# JacdacTactEc30_115.net
KiCad netlist of a schematic drawn in Altium Designer
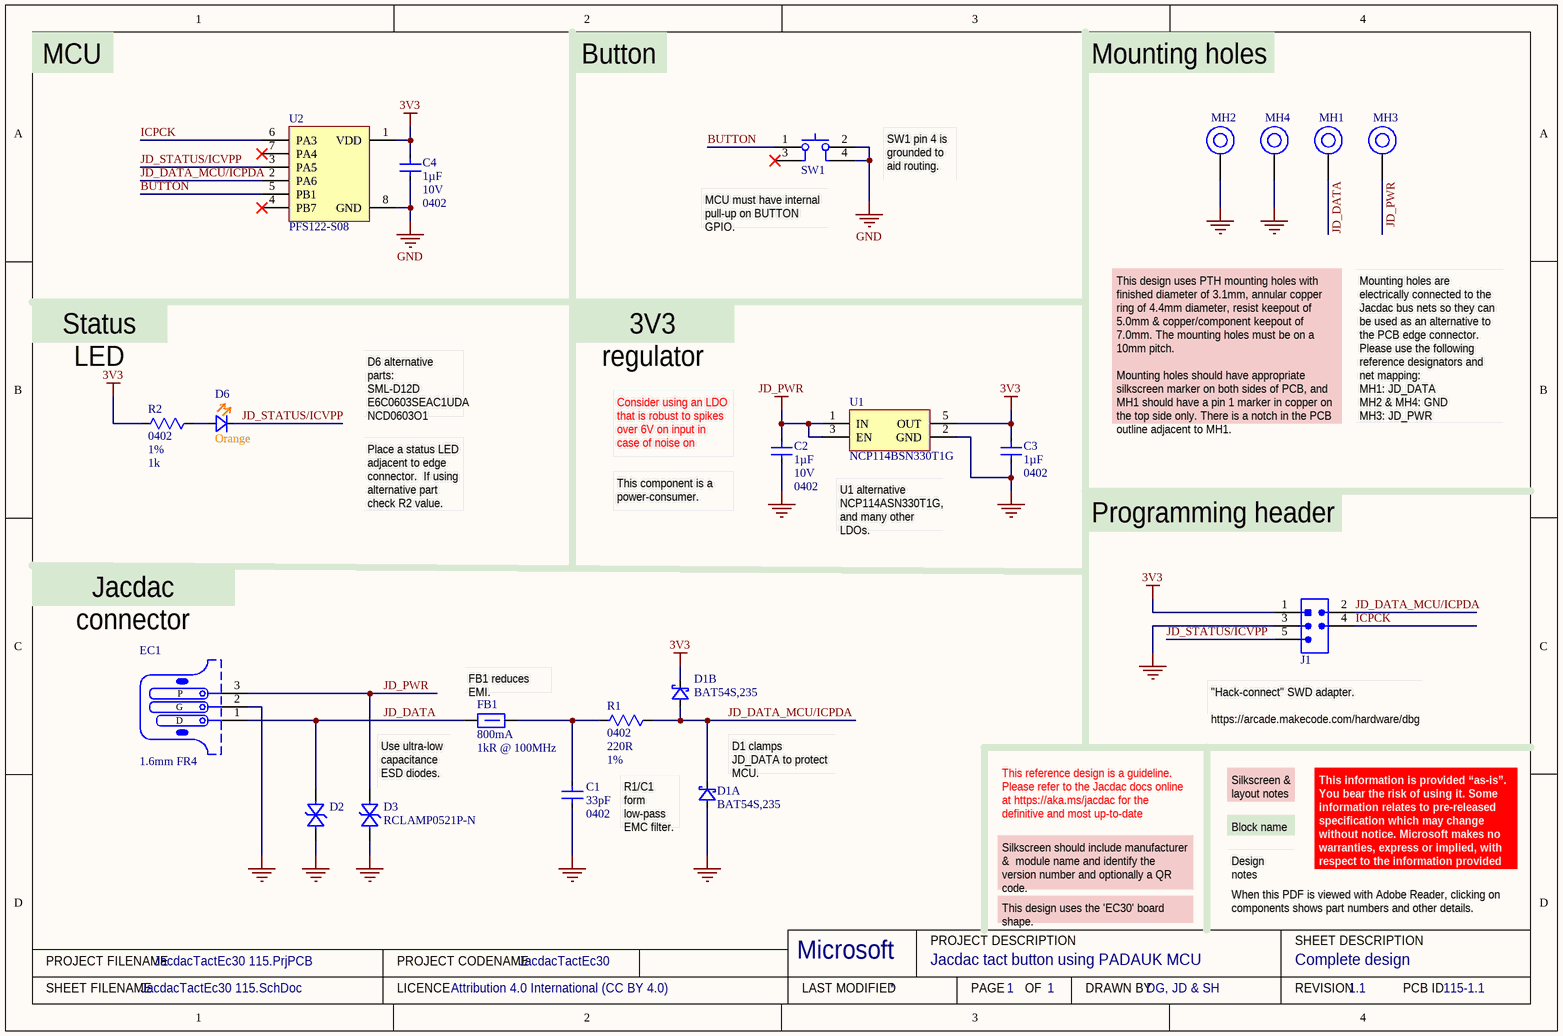
[diagram p0: JacdacTactEc30 115.SchDoc]

(export (version "E")
  (design (tool "Eeschema 10.0.6"))
  (components
    (comp (ref "C1")
      (value "CL05C330JB5NNNC")
      (footprint "C0402_0.55MM - without outline")
      (description "CAP CER 33PF 50V C0G/NP0 0402")
      (fields
        (field (name "MANUFACTURER") "Samsung")
        (field (name "CASE CODE (IMPERIAL)") "0402")
        (field (name "TOLERANCE") "5%")
        (field (name "CAPACITANCE") "33pF")
      )
      (libsource (lib "Samsung") (part "CL05C330JB5NNNC"))
    )
    (comp (ref "C2")
      (value "CL05A105KP5NNNC")
      (footprint "C0402_0.55MM - without outline")
      (description "CAP CER 1UF 10V X5R 0402")
      (fields
        (field (name "MANUFACTURER") "Samsung")
        (field (name "TOLERANCE") "10%")
        (field (name "CAPACITANCE") "1µF")
        (field (name "VOLTAGE RATING") "10V")
        (field (name "CASE CODE (IMPERIAL)") "0402")
        (field (name "CREATED") "DG")
        (field (name "CHECKED") "?")
      )
      (libsource (lib "Samsung") (part "CL05A105KP5NNNC"))
    )
    (comp (ref "C3")
      (value "CL05A105KP5NNNC")
      (footprint "C0402_0.55MM - without outline")
      (description "CAP CER 1UF 10V X5R 0402")
      (fields
        (field (name "MANUFACTURER") "Samsung")
        (field (name "TOLERANCE") "10%")
        (field (name "CAPACITANCE") "1µF")
        (field (name "CASE CODE (IMPERIAL)") "0402")
        (field (name "CREATED") "DG")
        (field (name "CHECKED") "?")
      )
      (libsource (lib "Samsung") (part "CL05A105KP5NNNC"))
    )
    (comp (ref "C4")
      (value "CL05A105KP5NNNC")
      (footprint "C0402_0.55MM - without outline")
      (description "CAP CER 1UF 10V X5R 0402")
      (fields
        (field (name "MANUFACTURER") "Samsung")
        (field (name "TOLERANCE") "10%")
        (field (name "CAPACITANCE") "1µF")
        (field (name "VOLTAGE RATING") "10V")
        (field (name "CASE CODE (IMPERIAL)") "0402")
        (field (name "CREATED") "DG")
        (field (name "CHECKED") "?")
      )
      (libsource (lib "Samsung") (part "CL05A105KP5NNNC"))
    )
    (comp (ref "D1")
      (value "BAT54S")
      (footprint "NXP-BAT54S-TO-236AB - without outline")
      (description "DIODE ARRAY SCHOTTKY 30V SOT23")
      (fields (field (name "MANUFACTURER") "Nexperia") (field (name "MANUFACTURER PART NUMBER") "BAT54S,235"))
      (libsource (lib "NXP") (part "BAT54S"))
    )
    (comp (ref "D2")
      (value "RCLAMP0521P-N")
      (footprint "0402:TVS 0402 - XL")
      (description "Bidirectional 5V (Max) 6V 16V 3.5A (8/20us) 0402 TVS RoHS")
      (fields
        (field (name "MANUFACTURER") "Born Semiconductor")
        (field (name "CREATED BY") "D Gakure")
        (field (name "CHECKED BY") "?")
      )
      (libsource (lib "BornSemiconductor") (part "RCLAMP0521P-N"))
    )
    (comp (ref "D3")
      (value "RCLAMP0521P-N")
      (footprint "0402:TVS 0402 - XL")
      (description "Bidirectional 5V (Max) 6V 16V 3.5A (8/20us) 0402 TVS RoHS")
      (fields
        (field (name "MANUFACTURER") "Born Semiconductor")
        (field (name "MANUFACTURER PART NUMBER") "RCLAMP0521P-N")
        (field (name "CREATED BY") "D Gakure")
        (field (name "CHECKED BY") "?")
      )
      (libsource (lib "BornSemiconductor") (part "RCLAMP0521P-N"))
    )
    (comp (ref "D6")
      (value "~")
      (footprint "0603 Orange - without outline")
      (description "LED ORANGE DIFFUSED 1608 SMD")
      (fields
        (field (name "MANUFACTURER") "Everlight Elec")
        (field (name "MANUFACTURER PART NUMBER") "19-217/S2C-AQ1R1B/3T")
        (field (name "COLOUR") "Orange")
      )
      (libsource (lib "EverlightElec") (part "19-217/S2C-AQ1R1B/3T"))
    )
    (comp (ref "EC1")
      (value "3 pin JACDAC edge connector")
      (footprint "JACDAC_edge_connector:JACDAC_EDGE_CONNECTOR_NO_TRACES")
      (description "3 pin Jacdac edge connector 1.27mm pitch")
      (fields
        (field (name "MANUFACTURER PART NUMBER") "JACDAC_EDGE_CONNECTOR")
        (field (name "PCB TYPE") "1.6mm FR4")
        (field (name "CHECKED BY") "?")
        (field (name "CREATED BY") "D. Gakure")
      )
      (libsource (lib "generic-con") (part "Jacdac edge connector"))
    )
    (comp (ref "FB1")
      (value "TDK MPZ1608S102ATA00")
      (footprint "TDK MPZ1608 0.8mm - without outline")
      (description "0603 1k@100MHz 0.8A chip")
      (fields
        (field (name "TOLERANCE") "25%")
        (field (name "MANUFACTURER") "TDK")
        (field (name "CURRENT RATING") "800mA")
        (field (name "IMPEDANCE") "1kR @ 100MHz")
      )
      (libsource (lib "TDK") (part "TDK MPZ1608S102ATA00"))
    )
    (comp (ref "J1")
      (value "Hack Connect Mini 1.27 mm pitch 2-row")
      (footprint "HackConnect:HACK_CONNECT_MINI_5_X_1_27_0.559mm_TH")
      (libsource (lib "generic-con") (part "HACK_CONNECT_MINI"))
    )
    (comp (ref "MH1")
      (value "MH_7.0MMK_4.4MMC_3.1MMD_PTH")
      (footprint "MH_7.0MMK_4.4MMC_3.1MMD_PTH:MH_7.0MMK_4.4MMC_3.1MMD_PTH")
      (description "Mounting Hole 7.0mm keepout, 4.4mm annualar ring and 3.1mm Drill PTH")
      (libsource (lib "generic") (part "MH_7.0MMK_4.4MMC_3.1MMD_PTH"))
    )
    (comp (ref "MH2")
      (value "MH_7.0MMK_4.4MMC_3.1MMD_PTH")
      (footprint "MH_7.0MMK_4.4MMC_3.1MMD_PTH:MH_7.0MMK_4.4MMC_3.1MMD_PTH")
      (description "Mounting Hole 7.0mm keepout, 4.4mm annualar ring and 3.1mm Drill PTH")
      (libsource (lib "generic") (part "MH_7.0MMK_4.4MMC_3.1MMD_PTH"))
    )
    (comp (ref "MH3")
      (value "MH_7.0MMK_4.4MMC_3.1MMD_PTH")
      (footprint "MH_7.0MMK_4.4MMC_3.1MMD_PTH:MH_7.0MMK_4.4MMC_3.1MMD_PTH")
      (description "Mounting Hole 7.0mm keepout, 4.4mm annualar ring and 3.1mm Drill PTH")
      (libsource (lib "generic") (part "MH_7.0MMK_4.4MMC_3.1MMD_PTH"))
    )
    (comp (ref "MH4")
      (value "MH_7.0MMK_4.4MMC_3.1MMD_PTH")
      (footprint "MH_7.0MMK_4.4MMC_3.1MMD_PTH:MH_7.0MMK_4.4MMC_3.1MMD_PTH")
      (description "Mounting Hole 7.0mm keepout, 4.4mm annualar ring and 3.1mm Drill PTH")
      (libsource (lib "generic") (part "MH_7.0MMK_4.4MMC_3.1MMD_PTH"))
    )
    (comp (ref "R1")
      (value "RC0402FR-07220RL")
      (footprint "R0402 - Without outline")
      (description "RES SMD 220 OHM 1% 1/16W 0402")
      (fields
        (field (name "MANUFACTURER") "Yageo")
        (field (name "CASE CODE (IMPERIAL)") "0402")
        (field (name "RESISTANCE") "220R")
        (field (name "TOLERANCE") "1%")
        (field (name "CREATED") "D.G")
        (field (name "CHECKED") "?")
      )
      (libsource (lib "Yageo") (part "RC0402FR-07220RL"))
    )
    (comp (ref "R2")
      (value "RC0402FR-071KL")
      (footprint "R0402 - Without outline")
      (description "RES SMD 1K OHM 1% 1/16W 0402")
      (fields
        (field (name "MANUFACTURER") "Yageo")
        (field (name "CASE CODE (IMPERIAL)") "0402")
        (field (name "TOLERANCE") "1%")
        (field (name "RESISTANCE") "1k")
        (field (name "CREATED") "D.G")
        (field (name "CHECKED") "?")
      )
      (libsource (lib "Yageo") (part "RC0402FR-071KL"))
    )
    (comp (ref "SW1")
      (value "Tact Wurth 430152050826")
      (footprint "Wurth 430152050836-WIDE")
      (description "6x6mm SPST 0.05A 12VDC SMD 260gf")
      (fields
        (field (name "MANUFACTURER") "Wurth Electronics")
        (field (name "MANUFACTURER PART NUMBER") "430152050826")
      )
      (libsource (lib "Wurth") (part "Tact Wurth 430152050826"))
    )
    (comp (ref "U1")
      (value "LDO 3.3V/300 mA")
      (footprint "ON_SEMI-SOT23-5 - without outline")
      (description "CMOS Low Dropout Regulator (LDO), 300 mA 3.3V, Non-Active Discharge, TSOP5")
      (fields
        (field (name "MANUFACTURER") "ON Semiconductor")
        (field (name "MANUFACTURER PART NUMBER") "NCP114BSN330T1G")
      )
      (libsource (lib "OnSemiconductor") (part "NCP114BSN330T1G"))
    )
    (comp (ref "U2")
      (value "PFS122-S08")
      (footprint "PADAUK-SOP-8:SOP-8")
      (description "8bit MTP MCU with 12-bit ADC")
      (fields (field (name "MANUFACTURER") "PADAUK") (field (name "MANUFACTURER PART NUMBER") "PFS122-S08"))
      (libsource (lib "PADAUK") (part "PFS122-SO8"))
    )
  )
  (nets
    (net (code "1") (name "/BUTTON") (class "Default")
      (node (ref "SW1") (pin "1") (pinfunction "1_1") (pintype "passive"))
      (node (ref "U2") (pin "5") (pinfunction "PB1_5") (pintype "passive"))
    )
    (net (code "2") (name "/ICPCK") (class "Default")
      (node (ref "J1") (pin "4") (pinfunction "SWCLK_4") (pintype "passive"))
      (node (ref "U2") (pin "6") (pinfunction "PA3_6") (pintype "passive"))
    )
    (net (code "3") (name "/JD_DATA") (class "Default")
      (node (ref "D2") (pin "1") (pinfunction "K_1") (pintype "passive"))
      (node (ref "EC1") (pin "1") (pinfunction "D_1") (pintype "passive"))
      (node (ref "FB1") (pin "1") (pinfunction "1_1") (pintype "passive"))
      (node (ref "MH1") (pin "1") (pinfunction "1_1") (pintype "passive"))
    )
    (net (code "4") (name "/JD_DATA_MCU{slash}ICPDA") (class "Default")
      (node (ref "D1") (pin "3") (pinfunction "A_3") (pintype "passive"))
      (node (ref "J1") (pin "2") (pinfunction "SWDIO_2") (pintype "passive"))
      (node (ref "R1") (pin "1") (pinfunction "1_1") (pintype "passive"))
      (node (ref "U2") (pin "2") (pinfunction "PA6_2") (pintype "passive"))
    )
    (net (code "5") (name "/JD_STATUS{slash}ICVPP") (class "Default")
      (node (ref "D6") (pin "1") (pinfunction "K_1") (pintype "passive"))
      (node (ref "J1") (pin "5") (pinfunction "RESET_5") (pintype "passive"))
      (node (ref "U2") (pin "3") (pinfunction "PA5_3") (pintype "passive"))
    )
    (net (code "6") (name "3V3") (class "Default")
      (node (ref "C3") (pin "2") (pinfunction "2_2") (pintype "passive"))
      (node (ref "C4") (pin "2") (pinfunction "2_2") (pintype "passive"))
      (node (ref "D1") (pin "2") (pinfunction "K_2") (pintype "passive"))
      (node (ref "J1") (pin "1") (pinfunction "VCC_1") (pintype "passive"))
      (node (ref "R2") (pin "2") (pinfunction "2_2") (pintype "passive"))
      (node (ref "U1") (pin "5") (pinfunction "OUT_5") (pintype "passive"))
      (node (ref "U2") (pin "1") (pinfunction "VDD_1") (pintype "passive"))
    )
    (net (code "7") (name "GND") (class "Default")
      (node (ref "C1") (pin "1") (pinfunction "1_1") (pintype "passive"))
      (node (ref "C2") (pin "1") (pinfunction "1_1") (pintype "passive"))
      (node (ref "C3") (pin "1") (pinfunction "1_1") (pintype "passive"))
      (node (ref "C4") (pin "1") (pinfunction "1_1") (pintype "passive"))
      (node (ref "D1") (pin "1") (pinfunction "A_1") (pintype "passive"))
      (node (ref "D2") (pin "2") (pinfunction "A_2") (pintype "passive"))
      (node (ref "D3") (pin "2") (pinfunction "A_2") (pintype "passive"))
      (node (ref "EC1") (pin "2") (pinfunction "G_2") (pintype "passive"))
      (node (ref "J1") (pin "3") (pinfunction "GND_3") (pintype "passive"))
      (node (ref "MH2") (pin "1") (pinfunction "1_1") (pintype "passive"))
      (node (ref "MH4") (pin "1") (pinfunction "1_1") (pintype "passive"))
      (node (ref "SW1") (pin "2") (pinfunction "2_2") (pintype "passive"))
      (node (ref "SW1") (pin "4") (pinfunction "4_4") (pintype "passive"))
      (node (ref "U1") (pin "2") (pinfunction "GND_2") (pintype "passive"))
      (node (ref "U2") (pin "8") (pinfunction "GND_8") (pintype "passive"))
    )
    (net (code "8") (name "JD_PWR") (class "Default")
      (node (ref "C2") (pin "2") (pinfunction "2_2") (pintype "passive"))
      (node (ref "D3") (pin "1") (pinfunction "K_1") (pintype "passive"))
      (node (ref "EC1") (pin "3") (pinfunction "P_3") (pintype "passive"))
      (node (ref "MH3") (pin "1") (pinfunction "1_1") (pintype "passive"))
      (node (ref "U1") (pin "1") (pinfunction "IN_1") (pintype "passive"))
      (node (ref "U1") (pin "3") (pinfunction "EN_3") (pintype "passive"))
    )
    (net (code "9") (name "Net-(C1-Pad2)") (class "Default")
      (node (ref "C1") (pin "2") (pinfunction "2_2") (pintype "passive"))
      (node (ref "FB1") (pin "2") (pinfunction "2_2") (pintype "passive"))
      (node (ref "R1") (pin "2") (pinfunction "2_2") (pintype "passive"))
    )
    (net (code "10") (name "Net-(D6-A)") (class "Default")
      (node (ref "D6") (pin "2") (pinfunction "A_2") (pintype "passive"))
      (node (ref "R2") (pin "1") (pinfunction "1_1") (pintype "passive"))
    )
    (net (code "11") (name "unconnected-(SW1-Pad3)") (class "Default")
      (node (ref "SW1") (pin "3") (pinfunction "3_3") (pintype "passive+no_connect"))
    )
    (net (code "12") (name "unconnected-(U2-PA4-Pad7)") (class "Default")
      (node (ref "U2") (pin "7") (pinfunction "PA4_7") (pintype "passive+no_connect"))
    )
    (net (code "13") (name "unconnected-(U2-PB7-Pad4)") (class "Default")
      (node (ref "U2") (pin "4") (pinfunction "PB7_4") (pintype "passive+no_connect"))
    )
  )
)
